# VoltageSourcePCBV2.net
KiCad netlist of a schematic drawn in EAGLE
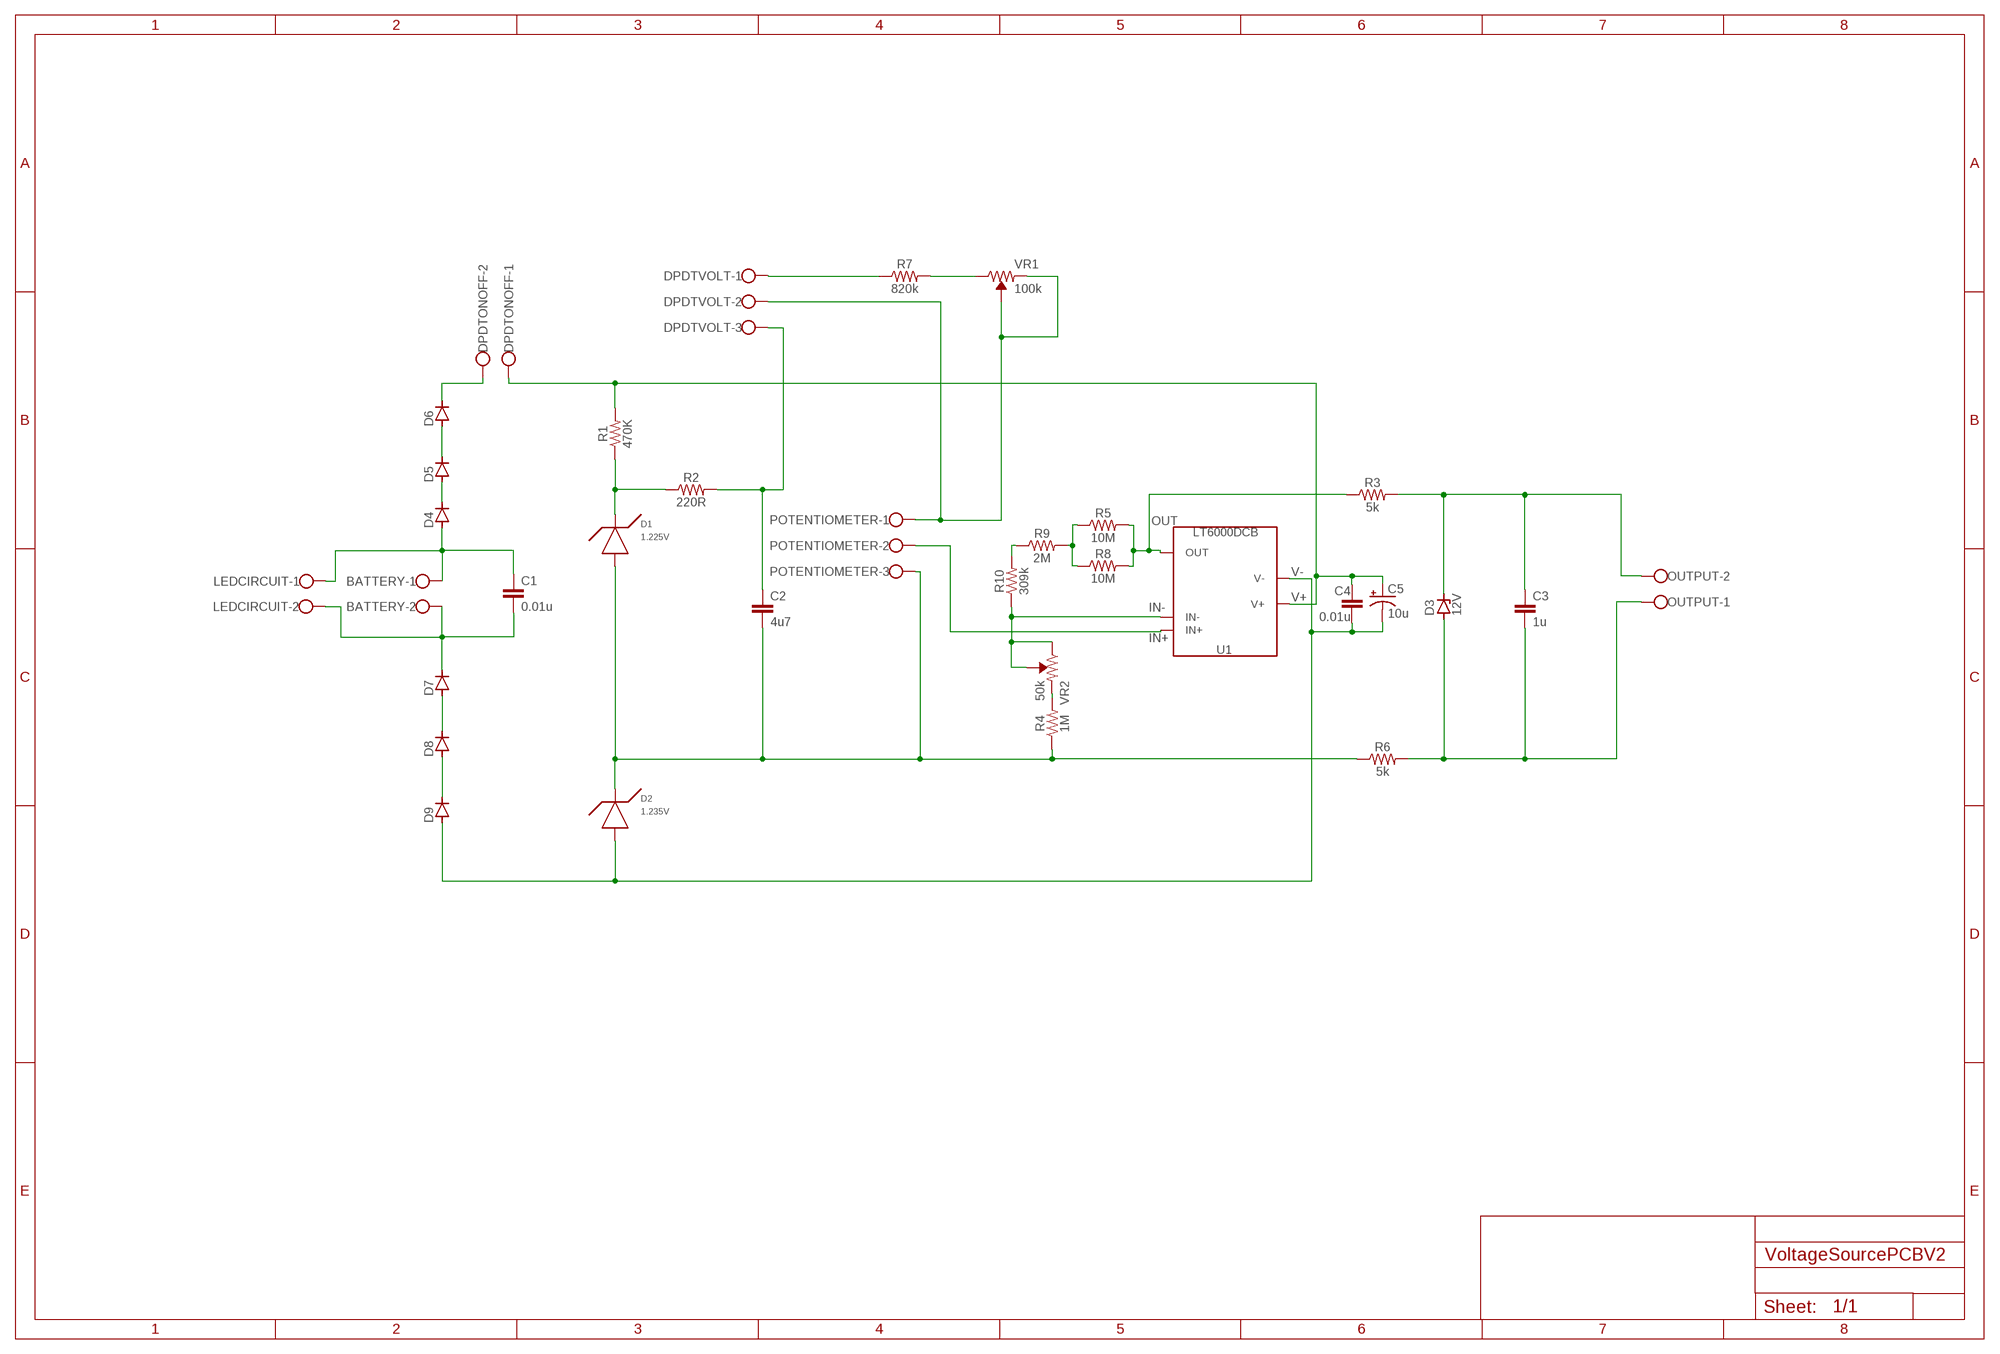
[diagram p0: schematic, sheet 1]

(export (version "E")
  (design (tool "Eeschema 10.0.6"))
  (components
    (comp (ref "BATTERY")
      (value "W237-102")
      (footprint "eagle-import:W237-102")
      (fields (field (name "MPN") "237-102"))
      (libsource (lib "eagle-import") (part "W237-102"))
    )
    (comp (ref "C1")
      (value "0.01u")
      (footprint "eagle-import:0805")
      (libsource (lib "eagle-import") (part "0.33UF/330NF-0805-50V-10%"))
    )
    (comp (ref "C2")
      (value "4u7")
      (footprint "eagle-import:0805")
      (libsource (lib "eagle-import") (part "0.33UF/330NF-0805-50V-10%"))
    )
    (comp (ref "C3")
      (value "1u")
      (footprint "eagle-import:0805")
      (libsource (lib "eagle-import") (part "0.33UF/330NF-0805-50V-10%"))
    )
    (comp (ref "C4")
      (value "0.01u")
      (footprint "eagle-import:0805")
      (libsource (lib "eagle-import") (part "0.33UF/330NF-0805-50V-10%"))
    )
    (comp (ref "C5")
      (value "10u")
      (footprint "eagle-import:EIA6032-NOM")
      (libsource (lib "eagle-import") (part "10UF-POLAR-EIA6032-25V-10%"))
    )
    (comp (ref "D1")
      (value "1.225V")
      (footprint "eagle-import:S8PACKAGE")
      (libsource (lib "eagle-import") (part "LT1004CS8SMD"))
    )
    (comp (ref "D2")
      (value "1.235V")
      (footprint "eagle-import:SOIC-8PACKAGE")
      (libsource (lib "eagle-import") (part "LM385BDSMD"))
    )
    (comp (ref "D3")
      (value "12V")
      (footprint "eagle-import:SOT23")
      (libsource (lib "eagle-import") (part "ZENER-DIODESOT23"))
    )
    (comp (ref "D4")
      (value "D-SOD123")
      (footprint "eagle-import:SOD123")
      (libsource (lib "eagle-import") (part "D-SOD123"))
    )
    (comp (ref "D5")
      (value "D-SOD123")
      (footprint "eagle-import:SOD123")
      (libsource (lib "eagle-import") (part "D-SOD123"))
    )
    (comp (ref "D6")
      (value "D-SOD123")
      (footprint "eagle-import:SOD123")
      (libsource (lib "eagle-import") (part "D-SOD123"))
    )
    (comp (ref "D7")
      (value "D-SOD123")
      (footprint "eagle-import:SOD123")
      (libsource (lib "eagle-import") (part "D-SOD123"))
    )
    (comp (ref "D8")
      (value "D-SOD123")
      (footprint "eagle-import:SOD123")
      (libsource (lib "eagle-import") (part "D-SOD123"))
    )
    (comp (ref "D9")
      (value "D-SOD123")
      (footprint "eagle-import:SOD123")
      (libsource (lib "eagle-import") (part "D-SOD123"))
    )
    (comp (ref "DPDTONOFF")
      (value "W237-102")
      (footprint "eagle-import:W237-102")
      (fields (field (name "MPN") "237-102"))
      (libsource (lib "eagle-import") (part "W237-102"))
    )
    (comp (ref "DPDTVOLT")
      (value "W237-103")
      (footprint "eagle-import:W237-103")
      (fields (field (name "MPN") "237-103"))
      (libsource (lib "eagle-import") (part "W237-103"))
    )
    (comp (ref "LEDCIRCUIT")
      (value "W237-102")
      (footprint "eagle-import:W237-102")
      (fields (field (name "MPN") "237-102"))
      (libsource (lib "eagle-import") (part "W237-102"))
    )
    (comp (ref "OUTPUT")
      (value "W237-102")
      (footprint "eagle-import:W237-102")
      (fields (field (name "MPN") "237-102"))
      (libsource (lib "eagle-import") (part "W237-102"))
    )
    (comp (ref "POTENTIOMETER")
      (value "W237-103")
      (footprint "eagle-import:W237-103")
      (fields (field (name "MPN") "237-103"))
      (libsource (lib "eagle-import") (part "W237-103"))
    )
    (comp (ref "R1")
      (value "470K")
      (footprint "eagle-import:0805")
      (libsource (lib "eagle-import") (part "RESISTOR0805"))
    )
    (comp (ref "R2")
      (value "220R")
      (footprint "eagle-import:0805")
      (libsource (lib "eagle-import") (part "RESISTOR0805"))
    )
    (comp (ref "R3")
      (value "5k")
      (footprint "eagle-import:0805")
      (libsource (lib "eagle-import") (part "RESISTOR0805"))
    )
    (comp (ref "R4")
      (value "1M")
      (footprint "eagle-import:0805")
      (libsource (lib "eagle-import") (part "RESISTOR0805"))
    )
    (comp (ref "R5")
      (value "10M")
      (footprint "eagle-import:0805")
      (libsource (lib "eagle-import") (part "RESISTOR0805"))
    )
    (comp (ref "R6")
      (value "5k")
      (footprint "eagle-import:0805")
      (libsource (lib "eagle-import") (part "RESISTOR0805"))
    )
    (comp (ref "R7")
      (value "820k")
      (footprint "eagle-import:0805")
      (libsource (lib "eagle-import") (part "RESISTOR0805"))
    )
    (comp (ref "R8")
      (value "10M")
      (footprint "eagle-import:0805")
      (libsource (lib "eagle-import") (part "RESISTOR0805"))
    )
    (comp (ref "R9")
      (value "2M")
      (footprint "eagle-import:0805")
      (libsource (lib "eagle-import") (part "RESISTOR0805"))
    )
    (comp (ref "R10")
      (value "309k")
      (footprint "eagle-import:0805")
      (libsource (lib "eagle-import") (part "RESISTOR0805"))
    )
    (comp (ref "U1")
      (value "LT6000DCB")
      (footprint "eagle-import:LT6000")
      (libsource (lib "eagle-import") (part "LT6000DCB"))
    )
    (comp (ref "VR1")
      (value "100k")
      (footprint "eagle-import:TRIMPOT-SMD-TC33X")
      (libsource (lib "eagle-import") (part "TRIMPOT-SMD-3MM-OPEN-1/10W-25%"))
    )
    (comp (ref "VR2")
      (value "50k")
      (footprint "eagle-import:TRIMPOT-SMD-TC33X")
      (libsource (lib "eagle-import") (part "TRIMPOT-SMD-3MM-OPEN-1/10W-25%"))
    )
  )
  (nets
    (net (code "1") (name "/IN+") (class "Default")
      (node (ref "POTENTIOMETER") (pin "2") (pinfunction "KL_2") (pintype "passive"))
      (node (ref "U1") (pin "3") (pinfunction "IN+_3") (pintype "input"))
    )
    (net (code "2") (name "/IN-") (class "Default")
      (node (ref "R10") (pin "1") (pinfunction "1_1") (pintype "passive"))
      (node (ref "U1") (pin "2") (pinfunction "IN-_2") (pintype "input"))
      (node (ref "VR2") (pin "1") (pinfunction "CW_1") (pintype "passive"))
      (node (ref "VR2") (pin "2") (pinfunction "WIPER_2") (pintype "passive"))
    )
    (net (code "3") (name "/OUT") (class "Default")
      (node (ref "R3") (pin "1") (pinfunction "1_1") (pintype "passive"))
      (node (ref "R5") (pin "2") (pinfunction "2_2") (pintype "passive"))
      (node (ref "R8") (pin "2") (pinfunction "2_2") (pintype "passive"))
      (node (ref "U1") (pin "4") (pinfunction "OUT_4") (pintype "output"))
    )
    (net (code "4") (name "/V+") (class "Default")
      (node (ref "C4") (pin "1") (pinfunction "1_1") (pintype "passive"))
      (node (ref "C5") (pin "A") (pinfunction "+_A") (pintype "passive"))
      (node (ref "DPDTONOFF") (pin "1") (pinfunction "KL_1") (pintype "passive"))
      (node (ref "R1") (pin "2") (pinfunction "2_2") (pintype "passive"))
      (node (ref "U1") (pin "6") (pinfunction "V+_6") (pintype "power_in"))
    )
    (net (code "5") (name "/V-") (class "Default")
      (node (ref "C4") (pin "2") (pinfunction "2_2") (pintype "passive"))
      (node (ref "C5") (pin "C") (pinfunction "-_C") (pintype "passive"))
      (node (ref "D2") (pin "4") (pinfunction "ANODE_4") (pintype "bidirectional"))
      (node (ref "D9") (pin "2") (pinfunction "A_2") (pintype "passive"))
      (node (ref "U1") (pin "5") (pinfunction "V-_5") (pintype "power_in"))
      (node (ref "U1") (pin "7") (pinfunction "V-_7") (pintype "power_in"))
    )
    (net (code "6") (name "Net-(BATTERYA-KL)") (class "Default")
      (node (ref "BATTERY") (pin "1") (pinfunction "KL_1") (pintype "passive"))
      (node (ref "C1") (pin "1") (pinfunction "1_1") (pintype "passive"))
      (node (ref "D4") (pin "2") (pinfunction "A_2") (pintype "passive"))
      (node (ref "LEDCIRCUIT") (pin "1") (pinfunction "KL_1") (pintype "passive"))
    )
    (net (code "7") (name "Net-(BATTERYB-KL)") (class "Default")
      (node (ref "BATTERY") (pin "2") (pinfunction "KL_2") (pintype "passive"))
      (node (ref "C1") (pin "2") (pinfunction "2_2") (pintype "passive"))
      (node (ref "D7") (pin "1") (pinfunction "C_1") (pintype "passive"))
      (node (ref "LEDCIRCUIT") (pin "2") (pinfunction "KL_2") (pintype "passive"))
    )
    (net (code "8") (name "Net-(D1-ANODE)") (class "Default")
      (node (ref "C2") (pin "2") (pinfunction "2_2") (pintype "passive"))
      (node (ref "D1") (pin "4") (pinfunction "ANODE_4") (pintype "bidirectional"))
      (node (ref "D2") (pin "8") (pinfunction "CATHODE_8") (pintype "bidirectional"))
      (node (ref "POTENTIOMETER") (pin "3") (pinfunction "KL_3") (pintype "passive"))
      (node (ref "R4") (pin "1") (pinfunction "1_1") (pintype "passive"))
      (node (ref "R6") (pin "1") (pinfunction "1_1") (pintype "passive"))
    )
    (net (code "9") (name "Net-(D1-CATHODE-Pad6)") (class "Default")
      (node (ref "D1") (pin "6") (pinfunction "CATHODE_6") (pintype "bidirectional"))
      (node (ref "D1") (pin "8") (pinfunction "CATHODE_8") (pintype "bidirectional"))
      (node (ref "R1") (pin "1") (pinfunction "1_1") (pintype "passive"))
      (node (ref "R2") (pin "1") (pinfunction "1_1") (pintype "passive"))
    )
    (net (code "10") (name "Net-(D3-A)") (class "Default")
      (node (ref "C3") (pin "2") (pinfunction "2_2") (pintype "passive"))
      (node (ref "D3") (pin "1") (pinfunction "A_1") (pintype "passive"))
      (node (ref "OUTPUT") (pin "1") (pinfunction "KL_1") (pintype "passive"))
      (node (ref "R6") (pin "2") (pinfunction "2_2") (pintype "passive"))
    )
    (net (code "11") (name "Net-(D3-C)") (class "Default")
      (node (ref "C3") (pin "1") (pinfunction "1_1") (pintype "passive"))
      (node (ref "D3") (pin "3") (pinfunction "C_3") (pintype "passive"))
      (node (ref "OUTPUT") (pin "2") (pinfunction "KL_2") (pintype "passive"))
      (node (ref "R3") (pin "2") (pinfunction "2_2") (pintype "passive"))
    )
    (net (code "12") (name "Net-(D4-C)") (class "Default")
      (node (ref "D4") (pin "1") (pinfunction "C_1") (pintype "passive"))
      (node (ref "D5") (pin "2") (pinfunction "A_2") (pintype "passive"))
    )
    (net (code "13") (name "Net-(D5-C)") (class "Default")
      (node (ref "D5") (pin "1") (pinfunction "C_1") (pintype "passive"))
      (node (ref "D6") (pin "2") (pinfunction "A_2") (pintype "passive"))
    )
    (net (code "14") (name "Net-(D6-C)") (class "Default")
      (node (ref "D6") (pin "1") (pinfunction "C_1") (pintype "passive"))
      (node (ref "DPDTONOFF") (pin "2") (pinfunction "KL_2") (pintype "passive"))
    )
    (net (code "15") (name "Net-(D7-A)") (class "Default")
      (node (ref "D7") (pin "2") (pinfunction "A_2") (pintype "passive"))
      (node (ref "D8") (pin "1") (pinfunction "C_1") (pintype "passive"))
    )
    (net (code "16") (name "Net-(D8-A)") (class "Default")
      (node (ref "D8") (pin "2") (pinfunction "A_2") (pintype "passive"))
      (node (ref "D9") (pin "1") (pinfunction "C_1") (pintype "passive"))
    )
    (net (code "17") (name "Net-(DPDTVOLTA-KL)") (class "Default")
      (node (ref "DPDTVOLT") (pin "1") (pinfunction "KL_1") (pintype "passive"))
      (node (ref "R7") (pin "1") (pinfunction "1_1") (pintype "passive"))
    )
    (net (code "18") (name "Net-(DPDTVOLTB-KL)") (class "Default")
      (node (ref "DPDTVOLT") (pin "2") (pinfunction "KL_2") (pintype "passive"))
      (node (ref "POTENTIOMETER") (pin "1") (pinfunction "KL_1") (pintype "passive"))
      (node (ref "VR1") (pin "2") (pinfunction "WIPER_2") (pintype "passive"))
      (node (ref "VR1") (pin "3") (pinfunction "CCW_3") (pintype "passive"))
    )
    (net (code "19") (name "Net-(DPDTVOLTC-KL)") (class "Default")
      (node (ref "C2") (pin "1") (pinfunction "1_1") (pintype "passive"))
      (node (ref "DPDTVOLT") (pin "3") (pinfunction "KL_3") (pintype "passive"))
      (node (ref "R2") (pin "2") (pinfunction "2_2") (pintype "passive"))
    )
    (net (code "20") (name "Net-(R5-Pad1)") (class "Default")
      (node (ref "R5") (pin "1") (pinfunction "1_1") (pintype "passive"))
      (node (ref "R8") (pin "1") (pinfunction "1_1") (pintype "passive"))
      (node (ref "R9") (pin "2") (pinfunction "2_2") (pintype "passive"))
    )
    (net (code "21") (name "Net-(R10-Pad2)") (class "Default")
      (node (ref "R10") (pin "2") (pinfunction "2_2") (pintype "passive"))
      (node (ref "R9") (pin "1") (pinfunction "1_1") (pintype "passive"))
    )
    (net (code "22") (name "Net-(VR1-CW)") (class "Default")
      (node (ref "R7") (pin "2") (pinfunction "2_2") (pintype "passive"))
      (node (ref "VR1") (pin "1") (pinfunction "CW_1") (pintype "passive"))
    )
    (net (code "23") (name "Net-(VR2-CCW)") (class "Default")
      (node (ref "R4") (pin "2") (pinfunction "2_2") (pintype "passive"))
      (node (ref "VR2") (pin "3") (pinfunction "CCW_3") (pintype "passive"))
    )
  )
)
